# aqc-dac-io-board.net
KiCad netlist of a schematic drawn in EAGLE
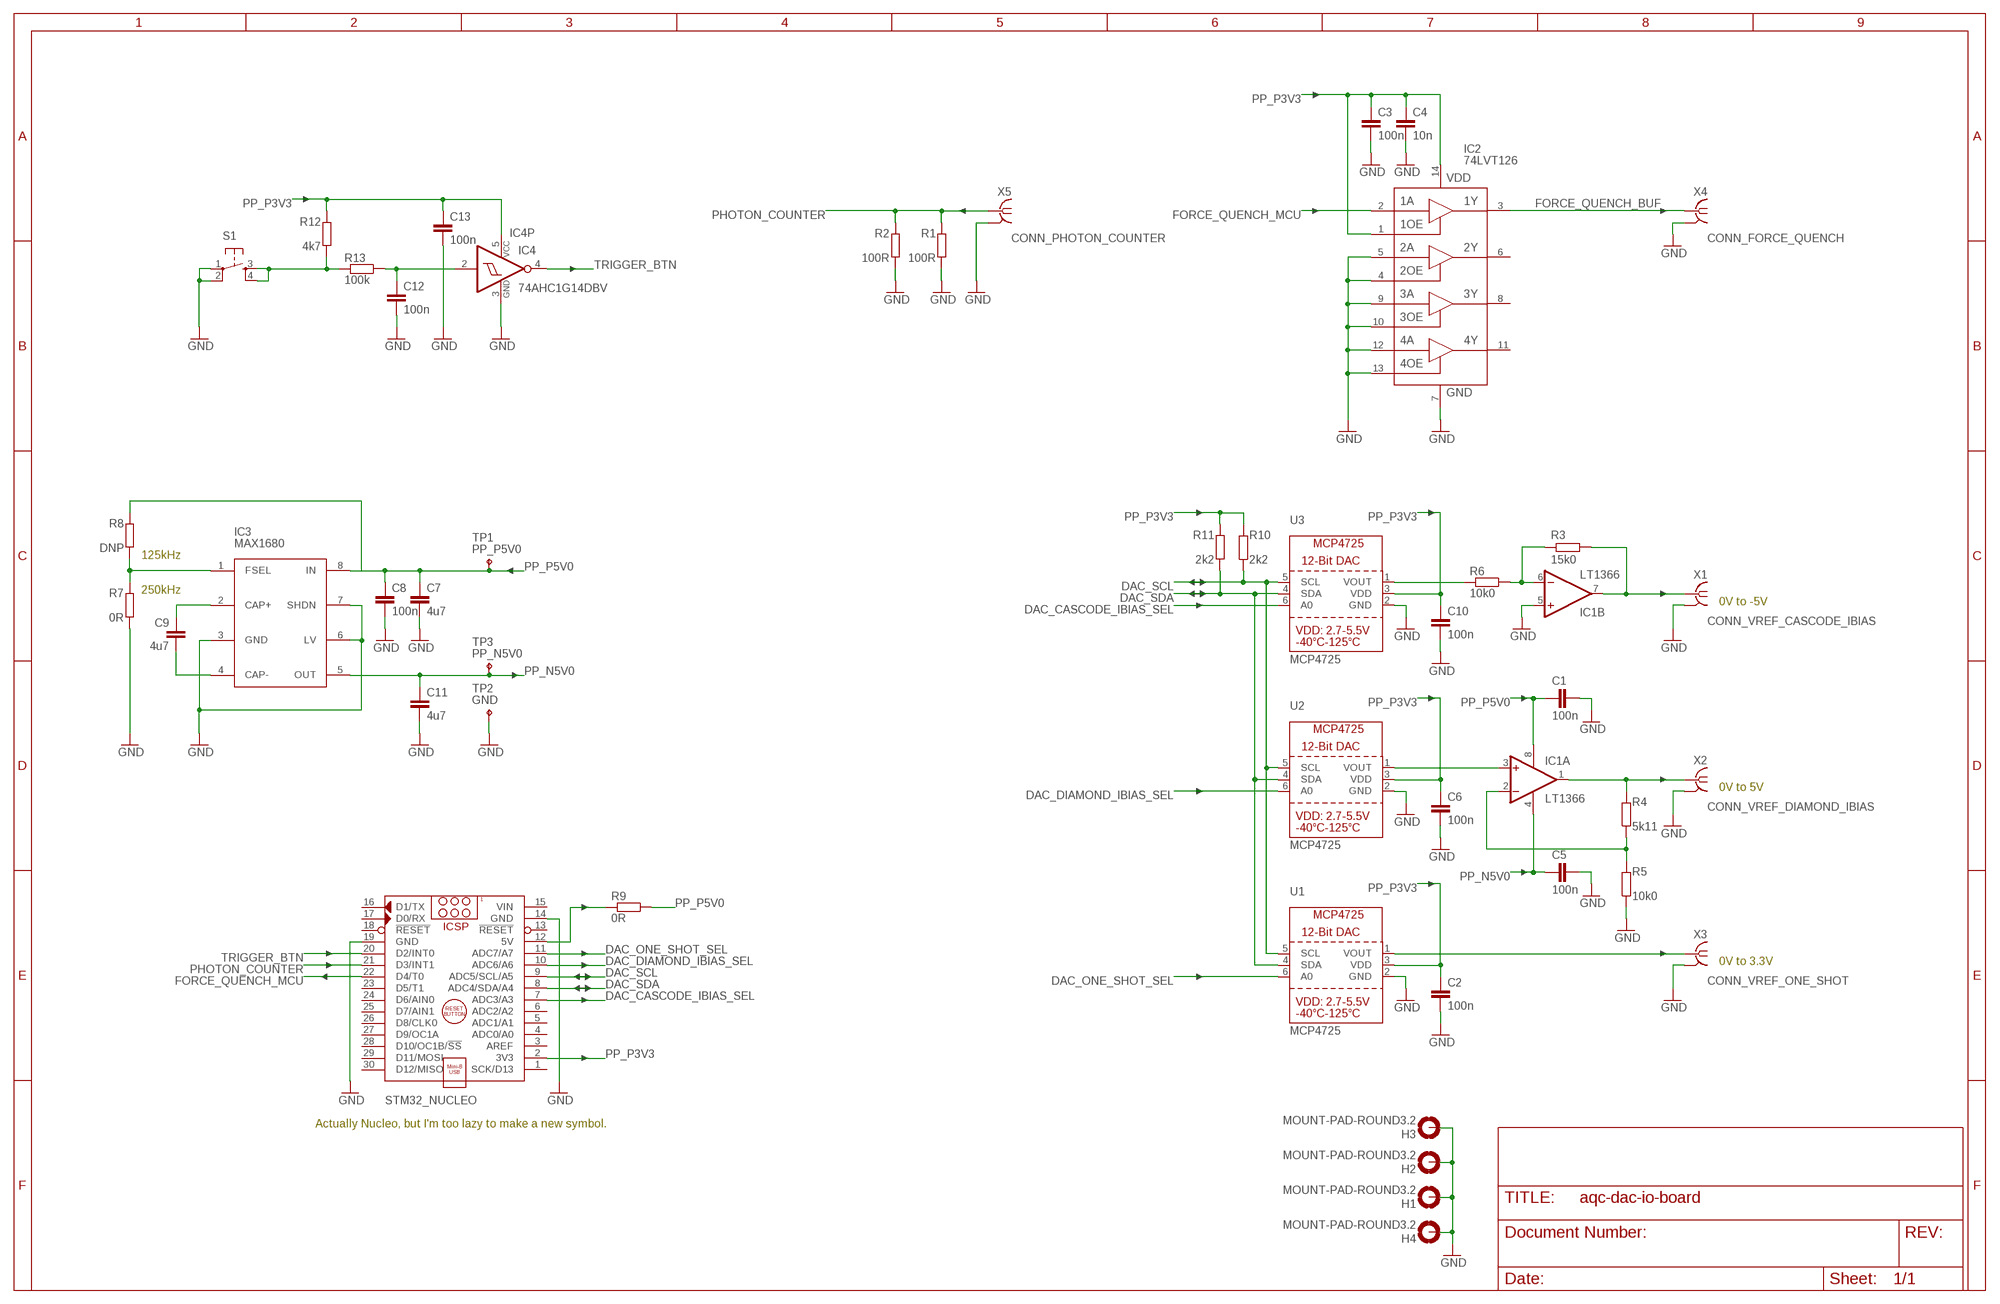
[diagram p0: schematic, sheet 1]

(export (version "E")
  (design (tool "Eeschema 10.0.6"))
  (components
    (comp (ref "C1")
      (value "100n")
      (footprint "eagle-import:C0603")
      (libsource (lib "eagle-import") (part "C-EUC0603"))
    )
    (comp (ref "C2")
      (value "100n")
      (footprint "eagle-import:C0603")
      (libsource (lib "eagle-import") (part "C-EUC0603"))
    )
    (comp (ref "C3")
      (value "100n")
      (footprint "eagle-import:C0603")
      (libsource (lib "eagle-import") (part "C-EUC0603"))
    )
    (comp (ref "C4")
      (value "10n")
      (footprint "eagle-import:C0603")
      (libsource (lib "eagle-import") (part "C-EUC0603"))
    )
    (comp (ref "C5")
      (value "100n")
      (footprint "eagle-import:C0603")
      (libsource (lib "eagle-import") (part "C-EUC0603"))
    )
    (comp (ref "C6")
      (value "100n")
      (footprint "eagle-import:C0603")
      (libsource (lib "eagle-import") (part "C-EUC0603"))
    )
    (comp (ref "C7")
      (value "4u7")
      (footprint "eagle-import:C0805")
      (libsource (lib "eagle-import") (part "C-EUC0805"))
    )
    (comp (ref "C8")
      (value "100n")
      (footprint "eagle-import:C0603")
      (libsource (lib "eagle-import") (part "C-EUC0603"))
    )
    (comp (ref "C9")
      (value "4u7")
      (footprint "eagle-import:C0805")
      (libsource (lib "eagle-import") (part "C-EUC0805"))
    )
    (comp (ref "C10")
      (value "100n")
      (footprint "eagle-import:C0603")
      (libsource (lib "eagle-import") (part "C-EUC0603"))
    )
    (comp (ref "C11")
      (value "4u7")
      (footprint "eagle-import:C0805")
      (libsource (lib "eagle-import") (part "C-EUC0805"))
    )
    (comp (ref "C12")
      (value "100n")
      (footprint "eagle-import:C0603")
      (libsource (lib "eagle-import") (part "C-EUC0603"))
    )
    (comp (ref "C13")
      (value "100n")
      (footprint "eagle-import:C0603")
      (libsource (lib "eagle-import") (part "C-EUC0603"))
    )
    (comp (ref "H1")
      (value "MOUNT-PAD-ROUND3.2")
      (footprint "eagle-import:3,2-PAD")
      (libsource (lib "eagle-import") (part "MOUNT-PAD-ROUND3.2"))
    )
    (comp (ref "H2")
      (value "MOUNT-PAD-ROUND3.2")
      (footprint "eagle-import:3,2-PAD")
      (libsource (lib "eagle-import") (part "MOUNT-PAD-ROUND3.2"))
    )
    (comp (ref "H3")
      (value "MOUNT-PAD-ROUND3.2")
      (footprint "eagle-import:3,2-PAD")
      (libsource (lib "eagle-import") (part "MOUNT-PAD-ROUND3.2"))
    )
    (comp (ref "H4")
      (value "MOUNT-PAD-ROUND3.2")
      (footprint "eagle-import:3,2-PAD")
      (libsource (lib "eagle-import") (part "MOUNT-PAD-ROUND3.2"))
    )
    (comp (ref "IC1")
      (value "LT1366")
      (footprint "eagle-import:SO08")
      (libsource (lib "eagle-import") (part "LT1366"))
    )
    (comp (ref "IC2")
      (value "74LVT126")
      (footprint "eagle-import:SO14")
      (libsource (lib "eagle-import") (part "74LVT126"))
    )
    (comp (ref "IC3")
      (value "MAX1680")
      (footprint "eagle-import:SO8")
      (libsource (lib "eagle-import") (part "MAX1680/1"))
    )
    (comp (ref "IC4")
      (value "74AHC1G14DBV")
      (footprint "eagle-import:SOT23-5")
      (libsource (lib "eagle-import") (part "741G14DBVAHC"))
    )
    (comp (ref "R1")
      (value "100R")
      (footprint "eagle-import:R0603")
      (libsource (lib "eagle-import") (part "R-EU_R0603"))
    )
    (comp (ref "R2")
      (value "100R")
      (footprint "eagle-import:R0603")
      (libsource (lib "eagle-import") (part "R-EU_R0603"))
    )
    (comp (ref "R3")
      (value "15k0")
      (footprint "eagle-import:R0603")
      (libsource (lib "eagle-import") (part "R-EU_R0603"))
    )
    (comp (ref "R4")
      (value "5k11")
      (footprint "eagle-import:R0603")
      (libsource (lib "eagle-import") (part "R-EU_R0603"))
    )
    (comp (ref "R5")
      (value "10k0")
      (footprint "eagle-import:R0603")
      (libsource (lib "eagle-import") (part "R-EU_R0603"))
    )
    (comp (ref "R6")
      (value "10k0")
      (footprint "eagle-import:R0603")
      (libsource (lib "eagle-import") (part "R-EU_R0603"))
    )
    (comp (ref "R7")
      (value "0R")
      (footprint "eagle-import:R0603")
      (libsource (lib "eagle-import") (part "R-EU_R0603"))
    )
    (comp (ref "R8")
      (value "DNP")
      (footprint "eagle-import:R0603")
      (libsource (lib "eagle-import") (part "R-EU_R0603"))
    )
    (comp (ref "R9")
      (value "0R")
      (footprint "eagle-import:R0603")
      (libsource (lib "eagle-import") (part "R-EU_R0603"))
    )
    (comp (ref "R10")
      (value "2k2")
      (footprint "eagle-import:R0603")
      (libsource (lib "eagle-import") (part "R-EU_R0603"))
    )
    (comp (ref "R11")
      (value "2k2")
      (footprint "eagle-import:R0603")
      (libsource (lib "eagle-import") (part "R-EU_R0603"))
    )
    (comp (ref "R12")
      (value "4k7")
      (footprint "eagle-import:R0603")
      (libsource (lib "eagle-import") (part "R-EU_R0603"))
    )
    (comp (ref "R13")
      (value "100k")
      (footprint "eagle-import:R0603")
      (libsource (lib "eagle-import") (part "R-EU_R0603"))
    )
    (comp (ref "S1")
      (value "TAC_SWITCHPTH")
      (footprint "eagle-import:TACTILE-PTH")
      (libsource (lib "eagle-import") (part "TAC_SWITCHPTH"))
    )
    (comp (ref "STM32_NUCLEO")
      (value "ARDUINO_NANO")
      (footprint "eagle-import:ARDUINO_NANO")
      (libsource (lib "eagle-import") (part "ARDUINO_NANO"))
    )
    (comp (ref "TP1")
      (value "PP_P5V0")
      (footprint "eagle-import:KEYSTONE_5000_MINIATURE")
      (libsource (lib "eagle-import") (part "KEYSTONE_5000"))
    )
    (comp (ref "TP2")
      (value "GND")
      (footprint "eagle-import:KEYSTONE_5000_MINIATURE")
      (libsource (lib "eagle-import") (part "KEYSTONE_5000"))
    )
    (comp (ref "TP3")
      (value "PP_N5V0")
      (footprint "eagle-import:KEYSTONE_5000_MINIATURE")
      (libsource (lib "eagle-import") (part "KEYSTONE_5000"))
    )
    (comp (ref "U1")
      (value "MCP4725")
      (footprint "eagle-import:SOT23-6")
      (libsource (lib "eagle-import") (part "DAC_MCP4725"))
    )
    (comp (ref "U2")
      (value "MCP4725")
      (footprint "eagle-import:SOT23-6")
      (libsource (lib "eagle-import") (part "DAC_MCP4725"))
    )
    (comp (ref "U3")
      (value "MCP4725")
      (footprint "eagle-import:SOT23-6")
      (libsource (lib "eagle-import") (part "DAC_MCP4725"))
    )
    (comp (ref "X1")
      (value "CONN_VREF_CASCODE_IBIAS")
      (footprint "eagle-import:J502-ND-142-0701-801_806")
      (fields (field (name "MF") "JOHNSON COMPONENTS") (field (name "MPN") "142-0701-801"))
      (libsource (lib "eagle-import") (part "SMA-142-0701-801/806"))
    )
    (comp (ref "X2")
      (value "CONN_VREF_DIAMOND_IBIAS")
      (footprint "eagle-import:J502-ND-142-0701-801_806")
      (fields (field (name "MF") "JOHNSON COMPONENTS") (field (name "MPN") "142-0701-801"))
      (libsource (lib "eagle-import") (part "SMA-142-0701-801/806"))
    )
    (comp (ref "X3")
      (value "CONN_VREF_ONE_SHOT")
      (footprint "eagle-import:J502-ND-142-0701-801_806")
      (fields (field (name "MF") "JOHNSON COMPONENTS") (field (name "MPN") "142-0701-801"))
      (libsource (lib "eagle-import") (part "SMA-142-0701-801/806"))
    )
    (comp (ref "X4")
      (value "CONN_FORCE_QUENCH")
      (footprint "eagle-import:J502-ND-142-0701-801_806")
      (fields (field (name "MF") "JOHNSON COMPONENTS") (field (name "MPN") "142-0701-801"))
      (libsource (lib "eagle-import") (part "SMA-142-0701-801/806"))
    )
    (comp (ref "X5")
      (value "CONN_PHOTON_COUNTER")
      (footprint "eagle-import:J502-ND-142-0701-801_806")
      (fields (field (name "MF") "JOHNSON COMPONENTS") (field (name "MPN") "142-0701-801"))
      (libsource (lib "eagle-import") (part "SMA-142-0701-801/806"))
    )
  )
  (nets
    (net (code "1") (name "/DAC_CASCODE_IBIAS_SEL") (class "Default")
      (node (ref "STM32_NUCLEO") (pin "7") (pinfunction "ADC3/A3_7") (pintype "bidirectional"))
      (node (ref "U3") (pin "6") (pinfunction "A0_6") (pintype "input"))
    )
    (net (code "2") (name "/DAC_DIAMOND_IBIAS_SEL") (class "Default")
      (node (ref "STM32_NUCLEO") (pin "10") (pinfunction "ADC6/A6_10") (pintype "bidirectional"))
      (node (ref "U2") (pin "6") (pinfunction "A0_6") (pintype "input"))
    )
    (net (code "3") (name "/DAC_ONE_SHOT_SEL") (class "Default")
      (node (ref "STM32_NUCLEO") (pin "11") (pinfunction "ADC7/A7_11") (pintype "bidirectional"))
      (node (ref "U1") (pin "6") (pinfunction "A0_6") (pintype "input"))
    )
    (net (code "4") (name "/DAC_SCL") (class "Default")
      (node (ref "R10") (pin "1") (pinfunction "1_1") (pintype "passive"))
      (node (ref "STM32_NUCLEO") (pin "9") (pinfunction "ADC5/SCL/A5_9") (pintype "bidirectional"))
      (node (ref "U1") (pin "5") (pinfunction "SCL_5") (pintype "bidirectional"))
      (node (ref "U2") (pin "5") (pinfunction "SCL_5") (pintype "bidirectional"))
      (node (ref "U3") (pin "5") (pinfunction "SCL_5") (pintype "bidirectional"))
    )
    (net (code "5") (name "/DAC_SDA") (class "Default")
      (node (ref "R11") (pin "1") (pinfunction "1_1") (pintype "passive"))
      (node (ref "STM32_NUCLEO") (pin "8") (pinfunction "ADC4/SDA/A4_8") (pintype "bidirectional"))
      (node (ref "U1") (pin "4") (pinfunction "SDA_4") (pintype "bidirectional"))
      (node (ref "U2") (pin "4") (pinfunction "SDA_4") (pintype "bidirectional"))
      (node (ref "U3") (pin "4") (pinfunction "SDA_4") (pintype "bidirectional"))
    )
    (net (code "6") (name "/FORCE_QUENCH_BUF") (class "Default")
      (node (ref "IC2") (pin "3") (pinfunction "1Y_3") (pintype "bidirectional"))
      (node (ref "X4") (pin "1") (pinfunction "1_1") (pintype "passive"))
    )
    (net (code "7") (name "/FORCE_QUENCH_MCU") (class "Default")
      (node (ref "IC2") (pin "2") (pinfunction "1A_2") (pintype "bidirectional"))
      (node (ref "STM32_NUCLEO") (pin "22") (pinfunction "D4/T0_22") (pintype "bidirectional"))
    )
    (net (code "8") (name "/PHOTON_COUNTER") (class "Default")
      (node (ref "R1") (pin "2") (pinfunction "2_2") (pintype "passive"))
      (node (ref "R2") (pin "2") (pinfunction "2_2") (pintype "passive"))
      (node (ref "STM32_NUCLEO") (pin "21") (pinfunction "D3/INT1_21") (pintype "bidirectional"))
      (node (ref "X5") (pin "1") (pinfunction "1_1") (pintype "passive"))
    )
    (net (code "9") (name "/PP_N5V0") (class "Default")
      (node (ref "C11") (pin "1") (pinfunction "1_1") (pintype "passive"))
      (node (ref "C5") (pin "1") (pinfunction "1_1") (pintype "passive"))
      (node (ref "IC1") (pin "4") (pinfunction "V-_4") (pintype "power_in"))
      (node (ref "IC3") (pin "5") (pinfunction "OUT_5") (pintype "bidirectional"))
      (node (ref "TP3") (pin "P$1") (pinfunction "P$1_P$1") (pintype "bidirectional"))
    )
    (net (code "10") (name "/PP_P3V3") (class "Default")
      (node (ref "C10") (pin "1") (pinfunction "1_1") (pintype "passive"))
      (node (ref "C13") (pin "1") (pinfunction "1_1") (pintype "passive"))
      (node (ref "C2") (pin "1") (pinfunction "1_1") (pintype "passive"))
      (node (ref "C3") (pin "1") (pinfunction "1_1") (pintype "passive"))
      (node (ref "C4") (pin "1") (pinfunction "1_1") (pintype "passive"))
      (node (ref "C6") (pin "1") (pinfunction "1_1") (pintype "passive"))
      (node (ref "IC2") (pin "1") (pinfunction "1OE_1") (pintype "bidirectional"))
      (node (ref "IC2") (pin "14") (pinfunction "VDD_14") (pintype "bidirectional"))
      (node (ref "IC4") (pin "5") (pinfunction "VCC_5") (pintype "power_in"))
      (node (ref "R10") (pin "2") (pinfunction "2_2") (pintype "passive"))
      (node (ref "R11") (pin "2") (pinfunction "2_2") (pintype "passive"))
      (node (ref "R12") (pin "2") (pinfunction "2_2") (pintype "passive"))
      (node (ref "STM32_NUCLEO") (pin "2") (pinfunction "3V3_2") (pintype "output"))
      (node (ref "U1") (pin "3") (pinfunction "VDD_3") (pintype "power_in"))
      (node (ref "U2") (pin "3") (pinfunction "VDD_3") (pintype "power_in"))
      (node (ref "U3") (pin "3") (pinfunction "VDD_3") (pintype "power_in"))
    )
    (net (code "11") (name "/PP_P5V0") (class "Default")
      (node (ref "C1") (pin "1") (pinfunction "1_1") (pintype "passive"))
      (node (ref "C7") (pin "1") (pinfunction "1_1") (pintype "passive"))
      (node (ref "C8") (pin "1") (pinfunction "1_1") (pintype "passive"))
      (node (ref "IC1") (pin "8") (pinfunction "V+_8") (pintype "power_in"))
      (node (ref "IC3") (pin "8") (pinfunction "IN_8") (pintype "bidirectional"))
      (node (ref "R8") (pin "2") (pinfunction "2_2") (pintype "passive"))
      (node (ref "R9") (pin "1") (pinfunction "1_1") (pintype "passive"))
      (node (ref "TP1") (pin "P$1") (pinfunction "P$1_P$1") (pintype "bidirectional"))
    )
    (net (code "12") (name "/TRIGGER_BTN") (class "Default")
      (node (ref "IC4") (pin "4") (pinfunction "O_4") (pintype "output"))
      (node (ref "STM32_NUCLEO") (pin "20") (pinfunction "D2/INT0_20") (pintype "bidirectional"))
    )
    (net (code "13") (name "/VIN") (class "Default")
      (node (ref "STM32_NUCLEO") (pin "15") (pinfunction "VIN_15") (pintype "power_in"))
    )
    (net (code "14") (name "GND") (class "Default")
      (node (ref "C1") (pin "2") (pinfunction "2_2") (pintype "passive"))
      (node (ref "C10") (pin "2") (pinfunction "2_2") (pintype "passive"))
      (node (ref "C11") (pin "2") (pinfunction "2_2") (pintype "passive"))
      (node (ref "C12") (pin "2") (pinfunction "2_2") (pintype "passive"))
      (node (ref "C13") (pin "2") (pinfunction "2_2") (pintype "passive"))
      (node (ref "C2") (pin "2") (pinfunction "2_2") (pintype "passive"))
      (node (ref "C3") (pin "2") (pinfunction "2_2") (pintype "passive"))
      (node (ref "C4") (pin "2") (pinfunction "2_2") (pintype "passive"))
      (node (ref "C5") (pin "2") (pinfunction "2_2") (pintype "passive"))
      (node (ref "C6") (pin "2") (pinfunction "2_2") (pintype "passive"))
      (node (ref "C7") (pin "2") (pinfunction "2_2") (pintype "passive"))
      (node (ref "C8") (pin "2") (pinfunction "2_2") (pintype "passive"))
      (node (ref "H1") (pin "B3,2") (pinfunction "MOUNT_B3,2") (pintype "passive"))
      (node (ref "H2") (pin "B3,2") (pinfunction "MOUNT_B3,2") (pintype "passive"))
      (node (ref "H3") (pin "B3,2") (pinfunction "MOUNT_B3,2") (pintype "passive"))
      (node (ref "H4") (pin "B3,2") (pinfunction "MOUNT_B3,2") (pintype "passive"))
      (node (ref "IC1") (pin "5") (pinfunction "+IN_5") (pintype "input"))
      (node (ref "IC2") (pin "10") (pinfunction "3OE_10") (pintype "bidirectional"))
      (node (ref "IC2") (pin "12") (pinfunction "4A_12") (pintype "bidirectional"))
      (node (ref "IC2") (pin "13") (pinfunction "4OE_13") (pintype "bidirectional"))
      (node (ref "IC2") (pin "4") (pinfunction "2OE_4") (pintype "bidirectional"))
      (node (ref "IC2") (pin "5") (pinfunction "2A_5") (pintype "bidirectional"))
      (node (ref "IC2") (pin "7") (pinfunction "GND_7") (pintype "bidirectional"))
      (node (ref "IC2") (pin "9") (pinfunction "3A_9") (pintype "bidirectional"))
      (node (ref "IC3") (pin "3") (pinfunction "GND_3") (pintype "bidirectional"))
      (node (ref "IC3") (pin "6") (pinfunction "LV_6") (pintype "bidirectional"))
      (node (ref "IC3") (pin "7") (pinfunction "SHDN_7") (pintype "bidirectional"))
      (node (ref "IC4") (pin "3") (pinfunction "GND_3") (pintype "power_in"))
      (node (ref "R1") (pin "1") (pinfunction "1_1") (pintype "passive"))
      (node (ref "R2") (pin "1") (pinfunction "1_1") (pintype "passive"))
      (node (ref "R5") (pin "1") (pinfunction "1_1") (pintype "passive"))
      (node (ref "R7") (pin "1") (pinfunction "1_1") (pintype "passive"))
      (node (ref "S1") (pin "1") (pinfunction "1_1") (pintype "passive"))
      (node (ref "S1") (pin "2") (pinfunction "2_2") (pintype "passive"))
      (node (ref "STM32_NUCLEO") (pin "14") (pinfunction "GND_14") (pintype "power_in"))
      (node (ref "STM32_NUCLEO") (pin "19") (pinfunction "GND_19") (pintype "power_in"))
      (node (ref "TP2") (pin "P$1") (pinfunction "P$1_P$1") (pintype "bidirectional"))
      (node (ref "U1") (pin "2") (pinfunction "GND_2") (pintype "power_in"))
      (node (ref "U2") (pin "2") (pinfunction "GND_2") (pintype "power_in"))
      (node (ref "U3") (pin "2") (pinfunction "GND_2") (pintype "power_in"))
      (node (ref "X1") (pin "G@1") (pinfunction "GND_G@1") (pintype "power_in"))
      (node (ref "X2") (pin "G@1") (pinfunction "GND_G@1") (pintype "power_in"))
      (node (ref "X3") (pin "G@1") (pinfunction "GND_G@1") (pintype "power_in"))
      (node (ref "X4") (pin "G@1") (pinfunction "GND_G@1") (pintype "power_in"))
      (node (ref "X5") (pin "G@1") (pinfunction "GND_G@1") (pintype "power_in"))
    )
    (net (code "15") (name "Net-(IC1A-+IN)") (class "Default")
      (node (ref "IC1") (pin "3") (pinfunction "+IN_3") (pintype "input"))
      (node (ref "U2") (pin "1") (pinfunction "VOUT_1") (pintype "output"))
    )
    (net (code "16") (name "Net-(IC1A--IN)") (class "Default")
      (node (ref "IC1") (pin "2") (pinfunction "-IN_2") (pintype "input"))
      (node (ref "R4") (pin "1") (pinfunction "1_1") (pintype "passive"))
      (node (ref "R5") (pin "2") (pinfunction "2_2") (pintype "passive"))
    )
    (net (code "17") (name "Net-(IC1A-OUT)") (class "Default")
      (node (ref "IC1") (pin "1") (pinfunction "OUT_1") (pintype "output"))
      (node (ref "R4") (pin "2") (pinfunction "2_2") (pintype "passive"))
      (node (ref "X2") (pin "1") (pinfunction "1_1") (pintype "passive"))
    )
    (net (code "18") (name "Net-(IC1B--IN)") (class "Default")
      (node (ref "IC1") (pin "6") (pinfunction "-IN_6") (pintype "input"))
      (node (ref "R3") (pin "2") (pinfunction "2_2") (pintype "passive"))
      (node (ref "R6") (pin "1") (pinfunction "1_1") (pintype "passive"))
    )
    (net (code "19") (name "Net-(IC1B-OUT)") (class "Default")
      (node (ref "IC1") (pin "7") (pinfunction "OUT_7") (pintype "output"))
      (node (ref "R3") (pin "1") (pinfunction "1_1") (pintype "passive"))
      (node (ref "X1") (pin "1") (pinfunction "1_1") (pintype "passive"))
    )
    (net (code "20") (name "Net-(IC3-CAP+)") (class "Default")
      (node (ref "C9") (pin "1") (pinfunction "1_1") (pintype "passive"))
      (node (ref "IC3") (pin "2") (pinfunction "CAP+_2") (pintype "bidirectional"))
    )
    (net (code "21") (name "Net-(IC3-CAP-)") (class "Default")
      (node (ref "C9") (pin "2") (pinfunction "2_2") (pintype "passive"))
      (node (ref "IC3") (pin "4") (pinfunction "CAP-_4") (pintype "bidirectional"))
    )
    (net (code "22") (name "Net-(IC3-FSEL)") (class "Default")
      (node (ref "IC3") (pin "1") (pinfunction "FSEL_1") (pintype "bidirectional"))
      (node (ref "R7") (pin "2") (pinfunction "2_2") (pintype "passive"))
      (node (ref "R8") (pin "1") (pinfunction "1_1") (pintype "passive"))
    )
    (net (code "23") (name "Net-(IC4A-I)") (class "Default")
      (node (ref "C12") (pin "1") (pinfunction "1_1") (pintype "passive"))
      (node (ref "IC4") (pin "2") (pinfunction "I_2") (pintype "input"))
      (node (ref "R13") (pin "1") (pinfunction "1_1") (pintype "passive"))
    )
    (net (code "24") (name "Net-(R12-Pad1)") (class "Default")
      (node (ref "R12") (pin "1") (pinfunction "1_1") (pintype "passive"))
      (node (ref "R13") (pin "2") (pinfunction "2_2") (pintype "passive"))
      (node (ref "S1") (pin "3") (pinfunction "3_3") (pintype "passive"))
      (node (ref "S1") (pin "4") (pinfunction "4_4") (pintype "passive"))
    )
    (net (code "25") (name "Net-(STM32_NUCLEO-5V)") (class "Default")
      (node (ref "R9") (pin "2") (pinfunction "2_2") (pintype "passive"))
      (node (ref "STM32_NUCLEO") (pin "12") (pinfunction "5V_12") (pintype "power_in"))
    )
    (net (code "26") (name "Net-(U1-VOUT)") (class "Default")
      (node (ref "U1") (pin "1") (pinfunction "VOUT_1") (pintype "output"))
      (node (ref "X3") (pin "1") (pinfunction "1_1") (pintype "passive"))
    )
    (net (code "27") (name "Net-(U3-VOUT)") (class "Default")
      (node (ref "R6") (pin "2") (pinfunction "2_2") (pintype "passive"))
      (node (ref "U3") (pin "1") (pinfunction "VOUT_1") (pintype "output"))
    )
    (net (code "28") (name "unconnected-(IC2-2Y-Pad6)") (class "Default")
      (node (ref "IC2") (pin "6") (pinfunction "2Y_6") (pintype "bidirectional"))
    )
    (net (code "29") (name "unconnected-(IC2-3Y-Pad8)") (class "Default")
      (node (ref "IC2") (pin "8") (pinfunction "3Y_8") (pintype "bidirectional"))
    )
    (net (code "30") (name "unconnected-(IC2-4Y-Pad11)") (class "Default")
      (node (ref "IC2") (pin "11") (pinfunction "4Y_11") (pintype "bidirectional"))
    )
    (net (code "31") (name "unconnected-(STM32_NUCLEO-ADC0{slash}A0-Pad4)") (class "Default")
      (node (ref "STM32_NUCLEO") (pin "4") (pinfunction "ADC0/A0_4") (pintype "bidirectional"))
    )
    (net (code "32") (name "unconnected-(STM32_NUCLEO-ADC1{slash}A1-Pad5)") (class "Default")
      (node (ref "STM32_NUCLEO") (pin "5") (pinfunction "ADC1/A1_5") (pintype "bidirectional"))
    )
    (net (code "33") (name "unconnected-(STM32_NUCLEO-ADC2{slash}A2-Pad6)") (class "Default")
      (node (ref "STM32_NUCLEO") (pin "6") (pinfunction "ADC2/A2_6") (pintype "bidirectional"))
    )
    (net (code "34") (name "unconnected-(STM32_NUCLEO-AREF-Pad3)") (class "Default")
      (node (ref "STM32_NUCLEO") (pin "3") (pinfunction "AREF_3") (pintype "input"))
    )
    (net (code "35") (name "unconnected-(STM32_NUCLEO-D0{slash}RX-Pad17)") (class "Default")
      (node (ref "STM32_NUCLEO") (pin "17") (pinfunction "D0/RX_17") (pintype "bidirectional"))
    )
    (net (code "36") (name "unconnected-(STM32_NUCLEO-D1{slash}TX-Pad16)") (class "Default")
      (node (ref "STM32_NUCLEO") (pin "16") (pinfunction "D1/TX_16") (pintype "bidirectional"))
    )
    (net (code "37") (name "unconnected-(STM32_NUCLEO-D5{slash}T1-Pad23)") (class "Default")
      (node (ref "STM32_NUCLEO") (pin "23") (pinfunction "D5/T1_23") (pintype "bidirectional"))
    )
    (net (code "38") (name "unconnected-(STM32_NUCLEO-D6{slash}AIN0-Pad24)") (class "Default")
      (node (ref "STM32_NUCLEO") (pin "24") (pinfunction "D6/AIN0_24") (pintype "bidirectional"))
    )
    (net (code "39") (name "unconnected-(STM32_NUCLEO-D7{slash}AIN1-Pad25)") (class "Default")
      (node (ref "STM32_NUCLEO") (pin "25") (pinfunction "D7/AIN1_25") (pintype "bidirectional"))
    )
    (net (code "40") (name "unconnected-(STM32_NUCLEO-D8{slash}CLK0-Pad26)") (class "Default")
      (node (ref "STM32_NUCLEO") (pin "26") (pinfunction "D8/CLK0_26") (pintype "bidirectional"))
    )
    (net (code "41") (name "unconnected-(STM32_NUCLEO-D9{slash}OC1A-Pad27)") (class "Default")
      (node (ref "STM32_NUCLEO") (pin "27") (pinfunction "D9/OC1A_27") (pintype "bidirectional"))
    )
    (net (code "42") (name "unconnected-(STM32_NUCLEO-D10{slash}OC1B{slash}~{SS}-Pad28)") (class "Default")
      (node (ref "STM32_NUCLEO") (pin "28") (pinfunction "D10/OC1B/~{SS}_28") (pintype "bidirectional"))
    )
    (net (code "43") (name "unconnected-(STM32_NUCLEO-D11{slash}MOSI-Pad29)") (class "Default")
      (node (ref "STM32_NUCLEO") (pin "29") (pinfunction "D11/MOSI_29") (pintype "bidirectional"))
    )
    (net (code "44") (name "unconnected-(STM32_NUCLEO-D12{slash}MISO-Pad30)") (class "Default")
      (node (ref "STM32_NUCLEO") (pin "30") (pinfunction "D12/MISO_30") (pintype "bidirectional"))
    )
    (net (code "45") (name "unconnected-(STM32_NUCLEO-SCK{slash}D13-Pad1)") (class "Default")
      (node (ref "STM32_NUCLEO") (pin "1") (pinfunction "SCK/D13_1") (pintype "bidirectional"))
    )
    (net (code "46") (name "unconnected-(STM32_NUCLEO-~{RESET}-Pad13)") (class "Default")
      (node (ref "STM32_NUCLEO") (pin "13") (pinfunction "~{RESET}_13") (pintype "input"))
    )
    (net (code "47") (name "unconnected-(STM32_NUCLEO-~{RESET}-Pad18)") (class "Default")
      (node (ref "STM32_NUCLEO") (pin "18") (pinfunction "~{RESET}_18") (pintype "input"))
    )
  )
)
